# Peripheral.net
KiCad netlist of a schematic drawn in Altium Designer
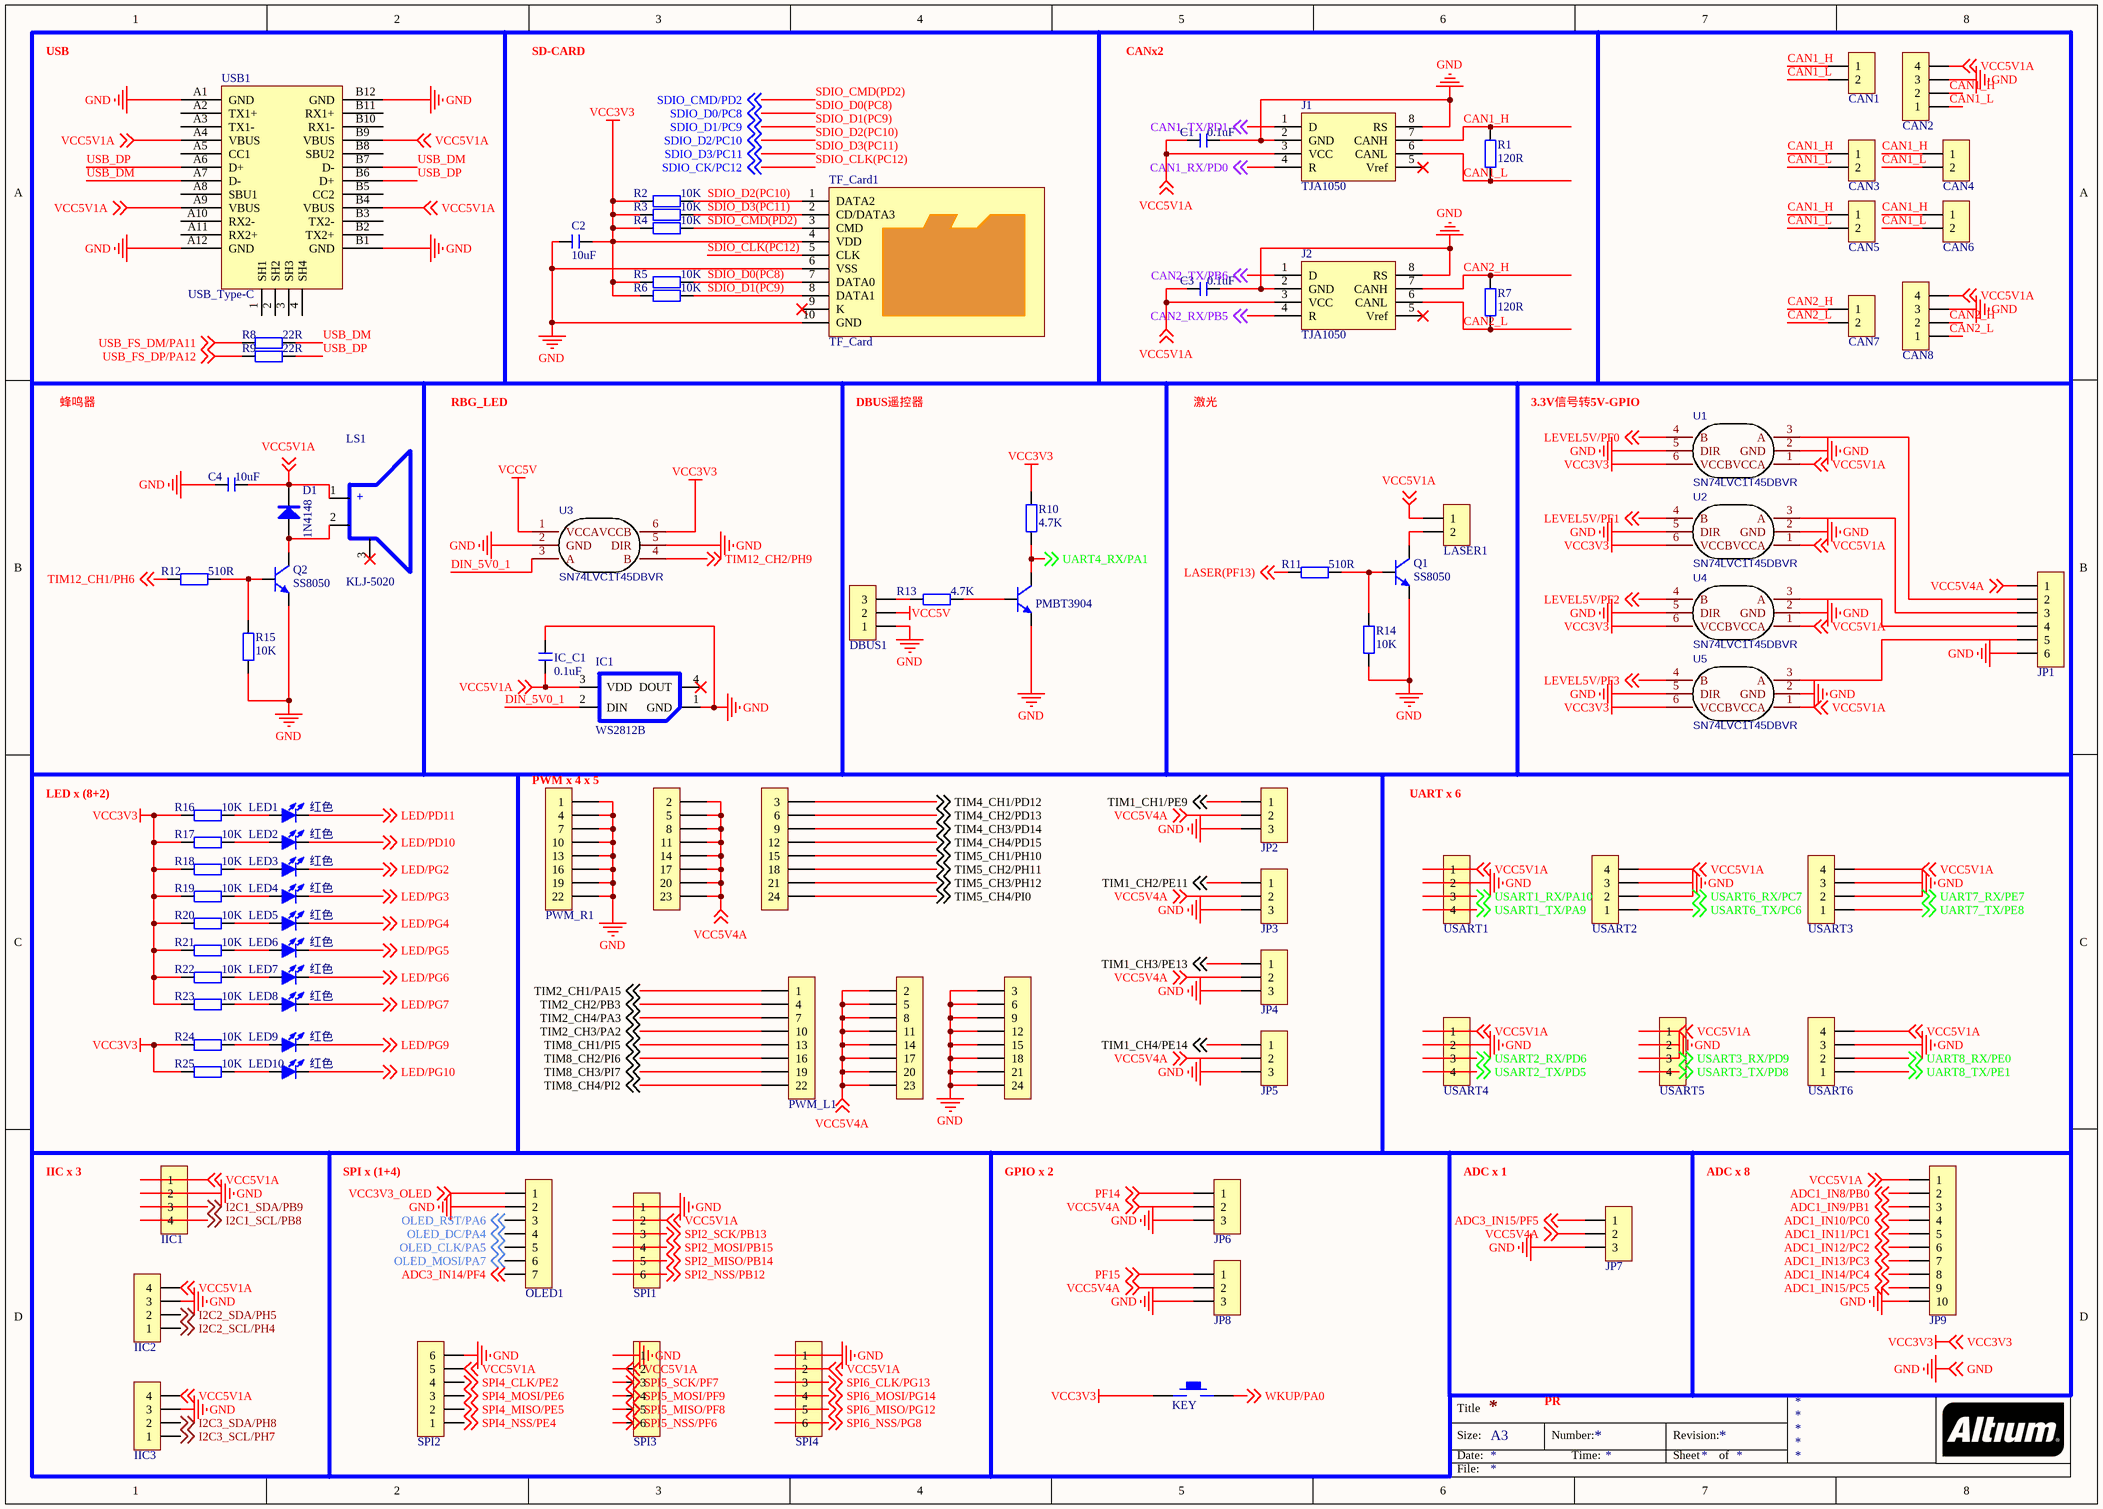
[diagram p0: Peripheral.SchDoc]

(export (version "E")
  (design (tool "Eeschema 10.0.6"))
  (components
    (comp (ref "C1")
      (value "0.1uF")
      (footprint "C 0402_L")
      (description "贴片电容")
      (libsource (lib "0.1 - 电阻-电容-电感") (part "C"))
    )
    (comp (ref "C2")
      (value "10uF")
      (footprint "C 0402_L")
      (description "贴片电容")
      (libsource (lib "0.1 - 电阻-电容-电感") (part "C"))
    )
    (comp (ref "C3")
      (value "0.1uF")
      (footprint "C 0402_L")
      (description "贴片电容")
      (libsource (lib "0.1 - 电阻-电容-电感") (part "C"))
    )
    (comp (ref "C4")
      (value "10uF")
      (footprint "C 0402_L")
      (description "贴片电容")
      (libsource (lib "0.1 - 电阻-电容-电感") (part "C"))
    )
    (comp (ref "CAN1")
      (value "HDR-1X2")
      (footprint "MX 1.25-LS-2P")
      (description "2P接插件")
      (libsource (lib "5.0 - 接插件-脚距1.25") (part "Header 2"))
    )
    (comp (ref "CAN2")
      (value "HDR-1X4")
      (footprint "MX 1.25-WS-4P")
      (description "4P接插件")
      (libsource (lib "") (part "Header 4_1"))
    )
    (comp (ref "CAN3")
      (value "HDR-1X2")
      (footprint "MX 1.25-LS-2P")
      (description "2P接插件")
      (libsource (lib "5.0 - 接插件-脚距1.25") (part "Header 2"))
    )
    (comp (ref "CAN4")
      (value "HDR-1X2")
      (footprint "MX 1.25-LS-2P")
      (description "2P接插件")
      (libsource (lib "5.0 - 接插件-脚距1.25") (part "Header 2"))
    )
    (comp (ref "CAN5")
      (value "HDR-1X2")
      (footprint "MX 1.25-LS-2P")
      (description "2P接插件")
      (libsource (lib "5.0 - 接插件-脚距1.25") (part "Header 2"))
    )
    (comp (ref "CAN6")
      (value "HDR-1X2")
      (footprint "MX 1.25-LS-2P")
      (description "2P接插件")
      (libsource (lib "5.0 - 接插件-脚距1.25") (part "Header 2"))
    )
    (comp (ref "CAN7")
      (value "HDR-1X2")
      (footprint "MX 1.25-LS-2P")
      (description "2P接插件")
      (libsource (lib "5.0 - 接插件-脚距1.25") (part "Header 2"))
    )
    (comp (ref "CAN8")
      (value "HDR-1X4")
      (footprint "MX 1.25-LS-4P")
      (description "4P接插件")
      (libsource (lib "") (part "Header 4_1"))
    )
    (comp (ref "D1")
      (value "1N4148")
      (footprint "SOD-323")
      (description "开关二极管")
      (libsource (lib "0.2 -  二极管-整流桥") (part "1N4148"))
    )
    (comp (ref "DBUS1")
      (value "HDR-1X3")
      (footprint "HDR2.54-WS-3P")
      (description "3P接插件")
      (libsource (lib "") (part "Header 3_1"))
    )
    (comp (ref "IC1")
      (value "WS2812B")
      (footprint "LED 3528-4Pin")
      (libsource (lib "mx_pcb_library") (part "WS2812B"))
    )
    (comp (ref "IC_C1")
      (value "0.1uF")
      (footprint "C 0402_L")
      (description "贴片电容")
      (libsource (lib "0.1 - 电阻-电容-电感") (part "C"))
    )
    (comp (ref "IIC1")
      (value "HDR-1X4")
      (footprint "MX 1.25-WS-4P")
      (description "4P接插件")
      (libsource (lib "5.0 - 接插件-脚距1.25") (part "Header 4"))
    )
    (comp (ref "IIC2")
      (value "HDR-1X4")
      (footprint "MX 1.25-LS-4P")
      (description "4P接插件")
      (libsource (lib "") (part "Header 4_1"))
    )
    (comp (ref "IIC3")
      (value "HDR-1X4")
      (footprint "MX 1.25-LS-4P")
      (description "4P接插件")
      (libsource (lib "") (part "Header 4_1"))
    )
    (comp (ref "J1")
      (value "TJA1050")
      (footprint "mx_pcb_library:SOIC-8_150mil")
      (description "CAN芯片")
      (libsource (lib "mx_pcb_library") (part "TJA1050"))
    )
    (comp (ref "J2")
      (value "TJA1050")
      (footprint "mx_pcb_library:SOIC-8_150mil")
      (description "CAN芯片")
      (libsource (lib "mx_pcb_library") (part "TJA1050"))
    )
    (comp (ref "JP1")
      (value "HDR-1X6")
      (footprint "MX 1.25-LS-6P")
      (description "6P接插件")
      (libsource (lib "5.0 - 接插件-脚距1.25") (part "Header 6"))
    )
    (comp (ref "JP2")
      (value "HDR-1X3")
      (footprint "HDR2.54-LI-3P")
      (description "3P接插件")
      (libsource (lib "5.3 - 接插件-脚距2.54 (100mil) ") (part "Header 3"))
    )
    (comp (ref "JP3")
      (value "HDR-1X3")
      (footprint "HDR2.54-LI-3P")
      (description "3P接插件")
      (libsource (lib "5.3 - 接插件-脚距2.54 (100mil) ") (part "Header 3"))
    )
    (comp (ref "JP4")
      (value "HDR-1X3")
      (footprint "HDR2.54-LI-3P")
      (description "3P接插件")
      (libsource (lib "5.3 - 接插件-脚距2.54 (100mil) ") (part "Header 3"))
    )
    (comp (ref "JP5")
      (value "HDR-1X3")
      (footprint "HDR2.54-LI-3P")
      (description "3P接插件")
      (libsource (lib "5.3 - 接插件-脚距2.54 (100mil) ") (part "Header 3"))
    )
    (comp (ref "JP6")
      (value "HDR-1X3")
      (footprint "HDR2.54-LI-3P")
      (description "3P接插件")
      (libsource (lib "5.3 - 接插件-脚距2.54 (100mil) ") (part "Header 3"))
    )
    (comp (ref "JP7")
      (value "HDR-1X3")
      (footprint "MX 1.25-WS-3P")
      (description "3P接插件")
      (libsource (lib "5.0 - 接插件-脚距1.25") (part "Header 3"))
    )
    (comp (ref "JP8")
      (value "HDR-1X3")
      (footprint "HDR2.54-LI-3P")
      (description "3P接插件")
      (libsource (lib "5.3 - 接插件-脚距2.54 (100mil) ") (part "Header 3"))
    )
    (comp (ref "JP9")
      (value "HDR-1X10")
      (footprint "MX 1.25-LS-10P")
      (description "10P接插件")
      (libsource (lib "5.0 - 接插件-脚距1.25") (part "Header 10"))
    )
    (comp (ref "LASER1")
      (value "HDR-1X2")
      (footprint "MX 1.25-LS-2P")
      (description "2P接插件")
      (libsource (lib "5.0 - 接插件-脚距1.25") (part "Header 2"))
    )
    (comp (ref "LED1")
      (value "红色")
      (footprint "LED 0805G")
      (description "贴片LED")
      (libsource (lib "0.3 - LED发光二极管") (part "LED-SMD"))
    )
    (comp (ref "LED2")
      (value "红色")
      (footprint "LED 0805G")
      (description "贴片LED")
      (libsource (lib "0.3 - LED发光二极管") (part "LED-SMD"))
    )
    (comp (ref "LED3")
      (value "红色")
      (footprint "LED 0805G")
      (description "贴片LED")
      (libsource (lib "0.3 - LED发光二极管") (part "LED-SMD"))
    )
    (comp (ref "LED4")
      (value "红色")
      (footprint "LED 0805G")
      (description "贴片LED")
      (libsource (lib "0.3 - LED发光二极管") (part "LED-SMD"))
    )
    (comp (ref "LED5")
      (value "红色")
      (footprint "LED 0805G")
      (description "贴片LED")
      (libsource (lib "0.3 - LED发光二极管") (part "LED-SMD"))
    )
    (comp (ref "LED6")
      (value "红色")
      (footprint "LED 0805G")
      (description "贴片LED")
      (libsource (lib "0.3 - LED发光二极管") (part "LED-SMD"))
    )
    (comp (ref "LED7")
      (value "红色")
      (footprint "LED 0805G")
      (description "贴片LED")
      (libsource (lib "0.3 - LED发光二极管") (part "LED-SMD"))
    )
    (comp (ref "LED8")
      (value "红色")
      (footprint "LED 0805G")
      (description "贴片LED")
      (libsource (lib "0.3 - LED发光二极管") (part "LED-SMD"))
    )
    (comp (ref "LED9")
      (value "红色")
      (footprint "LED 0805R")
      (description "贴片LED")
      (libsource (lib "0.3 - LED发光二极管") (part "LED-SMD"))
    )
    (comp (ref "LED10")
      (value "红色")
      (footprint "LED 0805R")
      (description "贴片LED")
      (libsource (lib "0.3 - LED发光二极管") (part "LED-SMD"))
    )
    (comp (ref "LS1")
      (value "KLJ-5020")
      (footprint "mx_pcb_library:BUZ-SMD_4P-L5.0-W5.0-P3.80-TL")
      (description "蜂鸣器")
      (libsource (lib "mx_pcb_library") (part "KLJ-5020"))
    )
    (comp (ref "OLED1")
      (value "HDR-1X7")
      (footprint "MX 1.25-WS-7P")
      (description "7P接插件")
      (libsource (lib "5.0 - 接插件-脚距1.25") (part "Header 7"))
    )
    (comp (ref "PWM_L1")
      (value "HDR3*8-left")
      (footprint "mx_pcb_library:PIN-3*8-2.54 - duplicate")
      (description "Connector")
      (libsource (lib "mx_pcb_library") (part "HDR3*8-left"))
    )
    (comp (ref "PWM_R1")
      (value "HDR3*8-right")
      (footprint "mx_pcb_library:PIN-3*8-2.54 - duplicate")
      (description "Connector")
      (libsource (lib "mx_pcb_library") (part "HDR3*8-right"))
    )
    (comp (ref "Q1")
      (value "SS8050")
      (footprint "SOT23-3L")
      (description "高频放大-NPN型")
      (libsource (lib "0.4 - 三极管") (part "8050-SMD"))
    )
    (comp (ref "Q2")
      (value "SS8050")
      (footprint "SOT23-3L")
      (description "高频放大-NPN型")
      (libsource (lib "0.4 - 三极管") (part "8050-SMD"))
    )
    (comp (ref "Q3")
      (value "PMBT3904")
      (footprint "mx_pcb_library:SOT-23-3")
      (description "NPN Bipolar Transistor")
      (libsource (lib "mx_pcb_library") (part "PMBT3904"))
    )
    (comp (ref "R1")
      (value "120R")
      (footprint "R 0402_L")
      (description "贴片电阻")
      (libsource (lib "0.1 - 电阻-电容-电感") (part "R"))
    )
    (comp (ref "R2")
      (value "10K")
      (footprint "R 0402_L")
      (description "贴片电阻")
      (libsource (lib "0.1 - 电阻-电容-电感") (part "R"))
    )
    (comp (ref "R3")
      (value "10K")
      (footprint "R 0402_L")
      (description "贴片电阻")
      (libsource (lib "0.1 - 电阻-电容-电感") (part "R"))
    )
    (comp (ref "R4")
      (value "10K")
      (footprint "R 0402_L")
      (description "贴片电阻")
      (libsource (lib "0.1 - 电阻-电容-电感") (part "R"))
    )
    (comp (ref "R5")
      (value "10K")
      (footprint "R 0402_L")
      (description "贴片电阻")
      (libsource (lib "0.1 - 电阻-电容-电感") (part "R"))
    )
    (comp (ref "R6")
      (value "10K")
      (footprint "R 0402_L")
      (description "贴片电阻")
      (libsource (lib "0.1 - 电阻-电容-电感") (part "R"))
    )
    (comp (ref "R7")
      (value "120R")
      (footprint "R 0402_L")
      (description "贴片电阻")
      (libsource (lib "0.1 - 电阻-电容-电感") (part "R"))
    )
    (comp (ref "R8")
      (value "22R")
      (footprint "R 0402_L")
      (description "贴片电阻")
      (libsource (lib "0.1 - 电阻-电容-电感") (part "R"))
    )
    (comp (ref "R9")
      (value "22R")
      (footprint "R 0402_L")
      (description "贴片电阻")
      (libsource (lib "0.1 - 电阻-电容-电感") (part "R"))
    )
    (comp (ref "R10")
      (value "4.7K")
      (footprint "R 0402_L")
      (description "贴片电阻")
      (libsource (lib "0.1 - 电阻-电容-电感") (part "R"))
    )
    (comp (ref "R11")
      (value "510R")
      (footprint "R 0402_L")
      (description "贴片电阻")
      (libsource (lib "0.1 - 电阻-电容-电感") (part "R"))
    )
    (comp (ref "R12")
      (value "510R")
      (footprint "R 0402_L")
      (description "贴片电阻")
      (libsource (lib "0.1 - 电阻-电容-电感") (part "R"))
    )
    (comp (ref "R13")
      (value "4.7K")
      (footprint "R 0402_L")
      (description "贴片电阻")
      (libsource (lib "0.1 - 电阻-电容-电感") (part "R"))
    )
    (comp (ref "R14")
      (value "10K")
      (footprint "R 0402_L")
      (description "贴片电阻")
      (libsource (lib "0.1 - 电阻-电容-电感") (part "R"))
    )
    (comp (ref "R15")
      (value "10K")
      (footprint "R 0402_L")
      (description "贴片电阻")
      (libsource (lib "0.1 - 电阻-电容-电感") (part "R"))
    )
    (comp (ref "R16")
      (value "10K")
      (footprint "R 0402_L")
      (description "贴片电阻")
      (libsource (lib "0.1 - 电阻-电容-电感") (part "R"))
    )
    (comp (ref "R17")
      (value "10K")
      (footprint "R 0402_L")
      (description "贴片电阻")
      (libsource (lib "0.1 - 电阻-电容-电感") (part "R"))
    )
    (comp (ref "R18")
      (value "10K")
      (footprint "R 0402_L")
      (description "贴片电阻")
      (libsource (lib "0.1 - 电阻-电容-电感") (part "R"))
    )
    (comp (ref "R19")
      (value "10K")
      (footprint "R 0402_L")
      (description "贴片电阻")
      (libsource (lib "0.1 - 电阻-电容-电感") (part "R"))
    )
    (comp (ref "R20")
      (value "10K")
      (footprint "R 0402_L")
      (description "贴片电阻")
      (libsource (lib "0.1 - 电阻-电容-电感") (part "R"))
    )
    (comp (ref "R21")
      (value "10K")
      (footprint "R 0402_L")
      (description "贴片电阻")
      (libsource (lib "0.1 - 电阻-电容-电感") (part "R"))
    )
    (comp (ref "R22")
      (value "10K")
      (footprint "R 0402_L")
      (description "贴片电阻")
      (libsource (lib "0.1 - 电阻-电容-电感") (part "R"))
    )
    (comp (ref "R23")
      (value "10K")
      (footprint "R 0402_L")
      (description "贴片电阻")
      (libsource (lib "0.1 - 电阻-电容-电感") (part "R"))
    )
    (comp (ref "R24")
      (value "10K")
      (footprint "R 0402_L")
      (description "贴片电阻")
      (libsource (lib "0.1 - 电阻-电容-电感") (part "R"))
    )
    (comp (ref "R25")
      (value "10K")
      (footprint "R 0402_L")
      (description "贴片电阻")
      (libsource (lib "0.1 - 电阻-电容-电感") (part "R"))
    )
    (comp (ref "RST1")
      (value "KEY")
      (footprint "mx_pcb_library:SMD-3.2*4.2")
      (libsource (lib "mx_pcb_library") (part "KEY_M"))
    )
    (comp (ref "SPI1")
      (value "HDR-1X6")
      (footprint "MX 1.25-WS-6P")
      (description "6P接插件")
      (libsource (lib "5.0 - 接插件-脚距1.25") (part "Header 6"))
    )
    (comp (ref "SPI2")
      (value "HDR-1X6")
      (footprint "MX 1.25-LS-6P")
      (description "6P接插件")
      (libsource (lib "") (part "Header 6_1"))
    )
    (comp (ref "SPI3")
      (value "HDR-1X6")
      (footprint "MX 1.25-WS-6P")
      (description "6P接插件")
      (libsource (lib "5.0 - 接插件-脚距1.25") (part "Header 6"))
    )
    (comp (ref "SPI4")
      (value "HDR-1X6")
      (footprint "MX 1.25-WS-6P")
      (description "6P接插件")
      (libsource (lib "5.0 - 接插件-脚距1.25") (part "Header 6"))
    )
    (comp (ref "TF_Card1")
      (value "TF_Card")
      (footprint "Micro SD")
      (description "TF卡座")
      (libsource (lib "0.8 - 网口-音频插座") (part "TF_Card"))
    )
    (comp (ref "U1")
      (value "SN74LVC1T45DBVR")
      (footprint "SOT-23-6_L2.9-W1.6-P0.95-LS2.8-BL")
      (fields (field (name "BOM_SUPPLIER PART") "C7843"))
      (libsource (lib "mx_pcb_library") (part "SN74LVC1T45DBVR"))
    )
    (comp (ref "U2")
      (value "SN74LVC1T45DBVR")
      (footprint "SOT-23-6_L2.9-W1.6-P0.95-LS2.8-BL")
      (fields (field (name "BOM_SUPPLIER PART") "C7843"))
      (libsource (lib "mx_pcb_library") (part "SN74LVC1T45DBVR"))
    )
    (comp (ref "U3")
      (value "SN74LVC1T45DBVR")
      (footprint "SOT-23-6_L2.9-W1.6-P0.95-LS2.8-BL")
      (fields (field (name "BOM_SUPPLIER PART") "C7843"))
      (libsource (lib "mx_pcb_library") (part "SN74LVC1T45DBVR"))
    )
    (comp (ref "U4")
      (value "SN74LVC1T45DBVR")
      (footprint "SOT-23-6_L2.9-W1.6-P0.95-LS2.8-BL")
      (fields (field (name "BOM_SUPPLIER PART") "C7843"))
      (libsource (lib "mx_pcb_library") (part "SN74LVC1T45DBVR"))
    )
    (comp (ref "U5")
      (value "SN74LVC1T45DBVR")
      (footprint "SOT-23-6_L2.9-W1.6-P0.95-LS2.8-BL")
      (fields (field (name "BOM_SUPPLIER PART") "C7843"))
      (libsource (lib "mx_pcb_library") (part "SN74LVC1T45DBVR"))
    )
    (comp (ref "USART1")
      (value "HDR-1X4")
      (footprint "MX 1.25-LS-4P")
      (description "4P接插件")
      (libsource (lib "5.0 - 接插件-脚距1.25") (part "Header 4"))
    )
    (comp (ref "USART2")
      (value "HDR-1X4")
      (footprint "MX 1.25-WS-4P")
      (description "4P接插件")
      (libsource (lib "") (part "Header 4_1"))
    )
    (comp (ref "USART3")
      (value "HDR-1X4")
      (footprint "MX 1.25-WS-4P")
      (description "4P接插件")
      (libsource (lib "") (part "Header 4_1"))
    )
    (comp (ref "USART4")
      (value "HDR-1X4")
      (footprint "MX 1.25-LS-4P")
      (description "4P接插件")
      (libsource (lib "5.0 - 接插件-脚距1.25") (part "Header 4"))
    )
    (comp (ref "USART5")
      (value "HDR-1X4")
      (footprint "MX 1.25-LS-4P")
      (description "4P接插件")
      (libsource (lib "5.0 - 接插件-脚距1.25") (part "Header 4"))
    )
    (comp (ref "USART6")
      (value "HDR-1X4")
      (footprint "MX 1.25-WS-4P")
      (description "4P接插件")
      (libsource (lib "") (part "Header 4_1"))
    )
    (comp (ref "USB1")
      (value "USB_Type-C")
      (footprint "mx_pcb_library:Type-C-TOP")
      (libsource (lib "mx_pcb_library") (part "USB_Type-C"))
    )
  )
  (nets
    (net (code "1") (name "/CAN1_H") (class "Default")
      (node (ref "CAN1") (pin "1") (pinfunction "1_1") (pintype "passive"))
      (node (ref "CAN2") (pin "2") (pinfunction "2_2") (pintype "passive"))
      (node (ref "CAN3") (pin "1") (pinfunction "1_1") (pintype "passive"))
      (node (ref "CAN4") (pin "1") (pinfunction "1_1") (pintype "passive"))
      (node (ref "CAN5") (pin "1") (pinfunction "1_1") (pintype "passive"))
      (node (ref "CAN6") (pin "1") (pinfunction "1_1") (pintype "passive"))
      (node (ref "J1") (pin "7") (pinfunction "CANH_7") (pintype "passive"))
      (node (ref "R1") (pin "2") (pinfunction "2_2") (pintype "passive"))
    )
    (net (code "2") (name "/CAN1_L") (class "Default")
      (node (ref "CAN1") (pin "2") (pinfunction "2_2") (pintype "passive"))
      (node (ref "CAN2") (pin "1") (pinfunction "1_1") (pintype "passive"))
      (node (ref "CAN3") (pin "2") (pinfunction "2_2") (pintype "passive"))
      (node (ref "CAN4") (pin "2") (pinfunction "2_2") (pintype "passive"))
      (node (ref "CAN5") (pin "2") (pinfunction "2_2") (pintype "passive"))
      (node (ref "CAN6") (pin "2") (pinfunction "2_2") (pintype "passive"))
      (node (ref "J1") (pin "6") (pinfunction "CANL_6") (pintype "passive"))
      (node (ref "R1") (pin "1") (pinfunction "1_1") (pintype "passive"))
    )
    (net (code "3") (name "/CAN2_H") (class "Default")
      (node (ref "CAN7") (pin "1") (pinfunction "1_1") (pintype "passive"))
      (node (ref "CAN8") (pin "2") (pinfunction "2_2") (pintype "passive"))
      (node (ref "J2") (pin "7") (pinfunction "CANH_7") (pintype "passive"))
      (node (ref "R7") (pin "2") (pinfunction "2_2") (pintype "passive"))
    )
    (net (code "4") (name "/CAN2_L") (class "Default")
      (node (ref "CAN7") (pin "2") (pinfunction "2_2") (pintype "passive"))
      (node (ref "CAN8") (pin "1") (pinfunction "1_1") (pintype "passive"))
      (node (ref "J2") (pin "6") (pinfunction "CANL_6") (pintype "passive"))
      (node (ref "R7") (pin "1") (pinfunction "1_1") (pintype "passive"))
    )
    (net (code "5") (name "/DIN_5V0_1") (class "Default")
      (node (ref "IC1") (pin "2") (pinfunction "DIN_2") (pintype "passive"))
      (node (ref "U3") (pin "3") (pinfunction "A_3") (pintype "passive"))
    )
    (net (code "6") (name "/USB_DM") (class "Default")
      (node (ref "R8") (pin "2") (pinfunction "2_2") (pintype "passive"))
      (node (ref "USB1") (pin "A7") (pinfunction "D-_A7") (pintype "passive"))
      (node (ref "USB1") (pin "B7") (pinfunction "D-_B7") (pintype "passive"))
    )
    (net (code "7") (name "/USB_DP") (class "Default")
      (node (ref "R9") (pin "2") (pinfunction "2_2") (pintype "passive"))
      (node (ref "USB1") (pin "A6") (pinfunction "D+_A6") (pintype "passive"))
      (node (ref "USB1") (pin "B6") (pinfunction "D+_B6") (pintype "passive"))
    )
    (net (code "8") (name "ADC1_IN8{slash}PB0") (class "Default")
      (node (ref "JP9") (pin "2") (pinfunction "2_2") (pintype "passive"))
    )
    (net (code "9") (name "ADC1_IN9{slash}PB1") (class "Default")
      (node (ref "JP9") (pin "3") (pinfunction "3_3") (pintype "passive"))
    )
    (net (code "10") (name "ADC1_IN10{slash}PC0") (class "Default")
      (node (ref "JP9") (pin "4") (pinfunction "4_4") (pintype "passive"))
    )
    (net (code "11") (name "ADC1_IN11{slash}PC1") (class "Default")
      (node (ref "JP9") (pin "5") (pinfunction "5_5") (pintype "passive"))
    )
    (net (code "12") (name "ADC1_IN12{slash}PC2") (class "Default")
      (node (ref "JP9") (pin "6") (pinfunction "6_6") (pintype "passive"))
    )
    (net (code "13") (name "ADC1_IN13{slash}PC3") (class "Default")
      (node (ref "JP9") (pin "7") (pinfunction "7_7") (pintype "passive"))
    )
    (net (code "14") (name "ADC1_IN14{slash}PC4") (class "Default")
      (node (ref "JP9") (pin "8") (pinfunction "8_8") (pintype "passive"))
    )
    (net (code "15") (name "ADC1_IN15{slash}PC5") (class "Default")
      (node (ref "JP9") (pin "9") (pinfunction "9_9") (pintype "passive"))
    )
    (net (code "16") (name "ADC3_IN14{slash}PF4") (class "Default")
      (node (ref "OLED1") (pin "7") (pinfunction "7_7") (pintype "passive"))
    )
    (net (code "17") (name "ADC3_IN15{slash}PF5") (class "Default")
      (node (ref "JP7") (pin "1") (pinfunction "1_1") (pintype "passive"))
    )
    (net (code "18") (name "CAN1_RX{slash}PD0") (class "Default")
      (node (ref "J1") (pin "4") (pinfunction "R_4") (pintype "passive"))
    )
    (net (code "19") (name "CAN1_TX{slash}PD1") (class "Default")
      (node (ref "J1") (pin "1") (pinfunction "D_1") (pintype "passive"))
    )
    (net (code "20") (name "CAN2_RX{slash}PB5") (class "Default")
      (node (ref "J2") (pin "4") (pinfunction "R_4") (pintype "passive"))
    )
    (net (code "21") (name "CAN2_TX{slash}PB6") (class "Default")
      (node (ref "J2") (pin "1") (pinfunction "D_1") (pintype "passive"))
    )
    (net (code "22") (name "GND") (class "Default")
      (node (ref "C1") (pin "1") (pinfunction "1_1") (pintype "passive"))
      (node (ref "C2") (pin "1") (pinfunction "1_1") (pintype "passive"))
      (node (ref "C3") (pin "1") (pinfunction "1_1") (pintype "passive"))
      (node (ref "C4") (pin "2") (pinfunction "2_2") (pintype "passive"))
      (node (ref "CAN2") (pin "3") (pinfunction "3_3") (pintype "passive"))
      (node (ref "CAN8") (pin "3") (pinfunction "3_3") (pintype "passive"))
      (node (ref "DBUS1") (pin "1") (pinfunction "1_1") (pintype "passive"))
      (node (ref "IC1") (pin "1") (pinfunction "GND_1") (pintype "passive"))
      (node (ref "IC_C1") (pin "1") (pinfunction "1_1") (pintype "passive"))
      (node (ref "IIC1") (pin "2") (pinfunction "2_2") (pintype "passive"))
      (node (ref "IIC2") (pin "3") (pinfunction "3_3") (pintype "passive"))
      (node (ref "IIC3") (pin "3") (pinfunction "3_3") (pintype "passive"))
      (node (ref "J1") (pin "2") (pinfunction "GND_2") (pintype "passive"))
      (node (ref "J1") (pin "8") (pinfunction "RS_8") (pintype "passive"))
      (node (ref "J2") (pin "2") (pinfunction "GND_2") (pintype "passive"))
      (node (ref "J2") (pin "8") (pinfunction "RS_8") (pintype "passive"))
      (node (ref "JP1") (pin "6") (pinfunction "6_6") (pintype "passive"))
      (node (ref "JP2") (pin "3") (pinfunction "3_3") (pintype "passive"))
      (node (ref "JP3") (pin "3") (pinfunction "3_3") (pintype "passive"))
      (node (ref "JP4") (pin "3") (pinfunction "3_3") (pintype "passive"))
      (node (ref "JP5") (pin "3") (pinfunction "3_3") (pintype "passive"))
      (node (ref "JP6") (pin "3") (pinfunction "3_3") (pintype "passive"))
      (node (ref "JP7") (pin "3") (pinfunction "3_3") (pintype "passive"))
      (node (ref "JP8") (pin "3") (pinfunction "3_3") (pintype "passive"))
      (node (ref "JP9") (pin "10") (pinfunction "10_10") (pintype "passive"))
      (node (ref "OLED1") (pin "2") (pinfunction "2_2") (pintype "passive"))
      (node (ref "PWM_L1") (pin "12") (pinfunction "12_12") (pintype "passive"))
      (node (ref "PWM_L1") (pin "15") (pinfunction "15_15") (pintype "passive"))
      (node (ref "PWM_L1") (pin "18") (pinfunction "18_18") (pintype "passive"))
      (node (ref "PWM_L1") (pin "21") (pinfunction "21_21") (pintype "passive"))
      (node (ref "PWM_L1") (pin "24") (pinfunction "24_24") (pintype "passive"))
      (node (ref "PWM_L1") (pin "3") (pinfunction "3_3") (pintype "passive"))
      (node (ref "PWM_L1") (pin "6") (pinfunction "6_6") (pintype "passive"))
      (node (ref "PWM_L1") (pin "9") (pinfunction "9_9") (pintype "passive"))
      (node (ref "PWM_R1") (pin "1") (pinfunction "1_1") (pintype "passive"))
      (node (ref "PWM_R1") (pin "10") (pinfunction "10_10") (pintype "passive"))
      (node (ref "PWM_R1") (pin "13") (pinfunction "13_13") (pintype "passive"))
      (node (ref "PWM_R1") (pin "16") (pinfunction "16_16") (pintype "passive"))
      (node (ref "PWM_R1") (pin "19") (pinfunction "19_19") (pintype "passive"))
      (node (ref "PWM_R1") (pin "22") (pinfunction "22_22") (pintype "passive"))
      (node (ref "PWM_R1") (pin "4") (pinfunction "4_4") (pintype "passive"))
      (node (ref "PWM_R1") (pin "7") (pinfunction "7_7") (pintype "passive"))
      (node (ref "Q1") (pin "2") (pinfunction "E_2") (pintype "passive"))
      (node (ref "Q2") (pin "2") (pinfunction "E_2") (pintype "passive"))
      (node (ref "Q3") (pin "2") (pinfunction "E_2") (pintype "passive"))
      (node (ref "R14") (pin "1") (pinfunction "1_1") (pintype "passive"))
      (node (ref "R15") (pin "1") (pinfunction "1_1") (pintype "passive"))
      (node (ref "SPI1") (pin "1") (pinfunction "1_1") (pintype "passive"))
      (node (ref "SPI2") (pin "6") (pinfunction "6_6") (pintype "passive"))
      (node (ref "SPI3") (pin "1") (pinfunction "1_1") (pintype "passive"))
      (node (ref "SPI4") (pin "1") (pinfunction "1_1") (pintype "passive"))
      (node (ref "TF_Card1") (pin "10") (pinfunction "GND_10") (pintype "passive"))
      (node (ref "TF_Card1") (pin "6") (pinfunction "VSS_6") (pintype "passive"))
      (node (ref "U1") (pin "2") (pinfunction "GND_2") (pintype "passive"))
      (node (ref "U1") (pin "5") (pinfunction "DIR_5") (pintype "passive"))
      (node (ref "U2") (pin "2") (pinfunction "GND_2") (pintype "passive"))
      (node (ref "U2") (pin "5") (pinfunction "DIR_5") (pintype "passive"))
      (node (ref "U3") (pin "2") (pinfunction "GND_2") (pintype "passive"))
      (node (ref "U3") (pin "5") (pinfunction "DIR_5") (pintype "passive"))
      (node (ref "U4") (pin "2") (pinfunction "GND_2") (pintype "passive"))
      (node (ref "U4") (pin "5") (pinfunction "DIR_5") (pintype "passive"))
      (node (ref "U5") (pin "2") (pinfunction "GND_2") (pintype "passive"))
      (node (ref "U5") (pin "5") (pinfunction "DIR_5") (pintype "passive"))
      (node (ref "USART1") (pin "2") (pinfunction "2_2") (pintype "passive"))
      (node (ref "USART2") (pin "3") (pinfunction "3_3") (pintype "passive"))
      (node (ref "USART3") (pin "3") (pinfunction "3_3") (pintype "passive"))
      (node (ref "USART4") (pin "2") (pinfunction "2_2") (pintype "passive"))
      (node (ref "USART5") (pin "2") (pinfunction "2_2") (pintype "passive"))
      (node (ref "USART6") (pin "3") (pinfunction "3_3") (pintype "passive"))
      (node (ref "USB1") (pin "A1") (pinfunction "GND_A1") (pintype "passive"))
      (node (ref "USB1") (pin "A12") (pinfunction "GND_A12") (pintype "passive"))
      (node (ref "USB1") (pin "B1") (pinfunction "GND_B1") (pintype "passive"))
      (node (ref "USB1") (pin "B12") (pinfunction "GND_B12") (pintype "passive"))
    )
    (net (code "23") (name "I2C1_SCL{slash}PB8") (class "Default")
      (node (ref "IIC1") (pin "4") (pinfunction "4_4") (pintype "passive"))
    )
    (net (code "24") (name "I2C1_SDA{slash}PB9") (class "Default")
      (node (ref "IIC1") (pin "3") (pinfunction "3_3") (pintype "passive"))
    )
    (net (code "25") (name "I2C2_SCL{slash}PH4") (class "Default")
      (node (ref "IIC2") (pin "1") (pinfunction "1_1") (pintype "passive"))
    )
    (net (code "26") (name "I2C2_SDA{slash}PH5") (class "Default")
      (node (ref "IIC2") (pin "2") (pinfunction "2_2") (pintype "passive"))
    )
    (net (code "27") (name "I2C3_SCL{slash}PH7") (class "Default")
      (node (ref "IIC3") (pin "1") (pinfunction "1_1") (pintype "passive"))
    )
    (net (code "28") (name "I2C3_SDA{slash}PH8") (class "Default")
      (node (ref "IIC3") (pin "2") (pinfunction "2_2") (pintype "passive"))
    )
    (net (code "29") (name "LASER(PF13)") (class "Default")
      (node (ref "R11") (pin "1") (pinfunction "1_1") (pintype "passive"))
    )
    (net (code "30") (name "LED{slash}PD10") (class "Default")
      (node (ref "LED2") (pin "2") (pinfunction "K_2") (pintype "passive"))
    )
    (net (code "31") (name "LED{slash}PD11") (class "Default")
      (node (ref "LED1") (pin "2") (pinfunction "K_2") (pintype "passive"))
    )
    (net (code "32") (name "LED{slash}PG2") (class "Default")
      (node (ref "LED3") (pin "2") (pinfunction "K_2") (pintype "passive"))
    )
    (net (code "33") (name "LED{slash}PG3") (class "Default")
      (node (ref "LED4") (pin "2") (pinfunction "K_2") (pintype "passive"))
    )
    (net (code "34") (name "LED{slash}PG4") (class "Default")
      (node (ref "LED5") (pin "2") (pinfunction "K_2") (pintype "passive"))
    )
    (net (code "35") (name "LED{slash}PG5") (class "Default")
      (node (ref "LED6") (pin "2") (pinfunction "K_2") (pintype "passive"))
    )
    (net (code "36") (name "LED{slash}PG6") (class "Default")
      (node (ref "LED7") (pin "2") (pinfunction "K_2") (pintype "passive"))
    )
    (net (code "37") (name "LED{slash}PG7") (class "Default")
      (node (ref "LED8") (pin "2") (pinfunction "K_2") (pintype "passive"))
    )
    (net (code "38") (name "LED{slash}PG9") (class "Default")
      (node (ref "LED9") (pin "2") (pinfunction "K_2") (pintype "passive"))
    )
    (net (code "39") (name "LED{slash}PG10") (class "Default")
      (node (ref "LED10") (pin "2") (pinfunction "K_2") (pintype "passive"))
    )
    (net (code "40") (name "LEVEL5V{slash}PF0") (class "Default")
      (node (ref "U1") (pin "4") (pinfunction "B_4") (pintype "passive"))
    )
    (net (code "41") (name "LEVEL5V{slash}PF1") (class "Default")
      (node (ref "U2") (pin "4") (pinfunction "B_4") (pintype "passive"))
    )
    (net (code "42") (name "LEVEL5V{slash}PF2") (class "Default")
      (node (ref "U4") (pin "4") (pinfunction "B_4") (pintype "passive"))
    )
    (net (code "43") (name "LEVEL5V{slash}PF3") (class "Default")
      (node (ref "U5") (pin "4") (pinfunction "B_4") (pintype "passive"))
    )
    (net (code "44") (name "Net-(D1-A)") (class "Default")
      (node (ref "D1") (pin "1") (pinfunction "A_1") (pintype "passive"))
      (node (ref "LS1") (pin "2") (pinfunction "2_2") (pintype "passive"))
      (node (ref "Q2") (pin "3") (pinfunction "C_3") (pintype "passive"))
    )
    (net (code "45") (name "Net-(DBUS1-Pad3)") (class "Default")
      (node (ref "DBUS1") (pin "3") (pinfunction "3_3") (pintype "passive"))
      (node (ref "R13") (pin "2") (pinfunction "2_2") (pintype "passive"))
    )
    (net (code "46") (name "Net-(LED1-A)") (class "Default")
      (node (ref "LED1") (pin "1") (pinfunction "A_1") (pintype "passive"))
      (node (ref "R16") (pin "2") (pinfunction "2_2") (pintype "passive"))
    )
    (net (code "47") (name "Net-(LED2-A)") (class "Default")
      (node (ref "LED2") (pin "1") (pinfunction "A_1") (pintype "passive"))
      (node (ref "R17") (pin "2") (pinfunction "2_2") (pintype "passive"))
    )
    (net (code "48") (name "Net-(LED3-A)") (class "Default")
      (node (ref "LED3") (pin "1") (pinfunction "A_1") (pintype "passive"))
      (node (ref "R18") (pin "2") (pinfunction "2_2") (pintype "passive"))
    )
    (net (code "49") (name "Net-(LED4-A)") (class "Default")
      (node (ref "LED4") (pin "1") (pinfunction "A_1") (pintype "passive"))
      (node (ref "R19") (pin "2") (pinfunction "2_2") (pintype "passive"))
    )
    (net (code "50") (name "Net-(LED5-A)") (class "Default")
      (node (ref "LED5") (pin "1") (pinfunction "A_1") (pintype "passive"))
      (node (ref "R20") (pin "2") (pinfunction "2_2") (pintype "passive"))
    )
    (net (code "51") (name "Net-(LED6-A)") (class "Default")
      (node (ref "LED6") (pin "1") (pinfunction "A_1") (pintype "passive"))
      (node (ref "R21") (pin "2") (pinfunction "2_2") (pintype "passive"))
    )
    (net (code "52") (name "Net-(LED7-A)") (class "Default")
      (node (ref "LED7") (pin "1") (pinfunction "A_1") (pintype "passive"))
      (node (ref "R22") (pin "2") (pinfunction "2_2") (pintype "passive"))
    )
    (net (code "53") (name "Net-(LED8-A)") (class "Default")
      (node (ref "LED8") (pin "1") (pinfunction "A_1") (pintype "passive"))
      (node (ref "R23") (pin "2") (pinfunction "2_2") (pintype "passive"))
    )
    (net (code "54") (name "Net-(LED9-A)") (class "Default")
      (node (ref "LED9") (pin "1") (pinfunction "A_1") (pintype "passive"))
      (node (ref "R24") (pin "2") (pinfunction "2_2") (pintype "passive"))
    )
    (net (code "55") (name "Net-(LED10-A)") (class "Default")
      (node (ref "LED10") (pin "1") (pinfunction "A_1") (pintype "passive"))
      (node (ref "R25") (pin "2") (pinfunction "2_2") (pintype "passive"))
    )
    (net (code "56") (name "Net-(Q1-B)") (class "Default")
      (node (ref "Q1") (pin "1") (pinfunction "B_1") (pintype "passive"))
      (node (ref "R11") (pin "2") (pinfunction "2_2") (pintype "passive"))
      (node (ref "R14") (pin "2") (pinfunction "2_2") (pintype "passive"))
    )
    (net (code "57") (name "Net-(Q1-C)") (class "Default")
      (node (ref "LASER1") (pin "2") (pinfunction "2_2") (pintype "passive"))
      (node (ref "Q1") (pin "3") (pinfunction "C_3") (pintype "passive"))
    )
    (net (code "58") (name "Net-(Q2-B)") (class "Default")
      (node (ref "Q2") (pin "1") (pinfunction "B_1") (pintype "passive"))
      (node (ref "R12") (pin "2") (pinfunction "2_2") (pintype "passive"))
      (node (ref "R15") (pin "2") (pinfunction "2_2") (pintype "passive"))
    )
    (net (code "59") (name "Net-(Q3-B)") (class "Default")
      (node (ref "Q3") (pin "1") (pinfunction "B_1") (pintype "passive"))
      (node (ref "R13") (pin "1") (pinfunction "1_1") (pintype "passive"))
    )
    (net (code "60") (name "Net-(U1-A)") (class "Default")
      (node (ref "JP1") (pin "2") (pinfunction "2_2") (pintype "passive"))
      (node (ref "U1") (pin "3") (pinfunction "A_3") (pintype "passive"))
    )
    (net (code "61") (name "Net-(U2-A)") (class "Default")
      (node (ref "JP1") (pin "3") (pinfunction "3_3") (pintype "passive"))
      (node (ref "U2") (pin "3") (pinfunction "A_3") (pintype "passive"))
    )
    (net (code "62") (name "Net-(U4-A)") (class "Default")
      (node (ref "JP1") (pin "4") (pinfunction "4_4") (pintype "passive"))
      (node (ref "U4") (pin "3") (pinfunction "A_3") (pintype "passive"))
    )
    (net (code "63") (name "Net-(U5-A)") (class "Default")
      (node (ref "JP1") (pin "5") (pinfunction "5_5") (pintype "passive"))
      (node (ref "U5") (pin "3") (pinfunction "A_3") (pintype "passive"))
    )
    (net (code "64") (name "OLED_CLK{slash}PA5") (class "Default")
      (node (ref "OLED1") (pin "5") (pinfunction "5_5") (pintype "passive"))
    )
    (net (code "65") (name "OLED_DC{slash}PA4") (class "Default")
      (node (ref "OLED1") (pin "4") (pinfunction "4_4") (pintype "passive"))
    )
    (net (code "66") (name "OLED_MOSI{slash}PA7") (class "Default")
      (node (ref "OLED1") (pin "6") (pinfunction "6_6") (pintype "passive"))
    )
    (net (code "67") (name "OLED_RST{slash}PA6") (class "Default")
      (node (ref "OLED1") (pin "3") (pinfunction "3_3") (pintype "passive"))
    )
    (net (code "68") (name "PF14") (class "Default")
      (node (ref "JP6") (pin "1") (pinfunction "1_1") (pintype "passive"))
    )
    (net (code "69") (name "PF15") (class "Default")
      (node (ref "JP8") (pin "1") (pinfunction "1_1") (pintype "passive"))
    )
    (net (code "70") (name "SDIO_CK{slash}PC12") (class "Default")
      (node (ref "TF_Card1") (pin "5") (pinfunction "CLK_5") (pintype "passive"))
    )
    (net (code "71") (name "SDIO_CMD{slash}PD2") (class "Default")
      (node (ref "R4") (pin "2") (pinfunction "2_2") (pintype "passive"))
      (node (ref "TF_Card1") (pin "3") (pinfunction "CMD_3") (pintype "passive"))
    )
    (net (code "72") (name "SDIO_D0{slash}PC8") (class "Default")
      (node (ref "R5") (pin "2") (pinfunction "2_2") (pintype "passive"))
      (node (ref "TF_Card1") (pin "7") (pinfunction "DATA0_7") (pintype "passive"))
    )
    (net (code "73") (name "SDIO_D1{slash}PC9") (class "Default")
      (node (ref "R6") (pin "2") (pinfunction "2_2") (pintype "passive"))
      (node (ref "TF_Card1") (pin "8") (pinfunction "DATA1_8") (pintype "passive"))
    )
    (net (code "74") (name "SDIO_D2{slash}PC10") (class "Default")
      (node (ref "R2") (pin "2") (pinfunction "2_2") (pintype "passive"))
      (node (ref "TF_Card1") (pin "1") (pinfunction "DATA2_1") (pintype "passive"))
    )
    (net (code "75") (name "SDIO_D3{slash}PC11") (class "Default")
      (node (ref "R3") (pin "2") (pinfunction "2_2") (pintype "passive"))
      (node (ref "TF_Card1") (pin "2") (pinfunction "CD/DATA3_2") (pintype "passive"))
    )
    (net (code "76") (name "SPI2_MISO{slash}PB14") (class "Default")
      (node (ref "SPI1") (pin "5") (pinfunction "5_5") (pintype "passive"))
    )
    (net (code "77") (name "SPI2_MOSI{slash}PB15") (class "Default")
      (node (ref "SPI1") (pin "4") (pinfunction "4_4") (pintype "passive"))
    )
    (net (code "78") (name "SPI2_NSS{slash}PB12") (class "Default")
      (node (ref "SPI1") (pin "6") (pinfunction "6_6") (pintype "passive"))
    )
    (net (code "79") (name "SPI2_SCK{slash}PB13") (class "Default")
      (node (ref "SPI1") (pin "3") (pinfunction "3_3") (pintype "passive"))
    )
    (net (code "80") (name "SPI4_CLK{slash}PE2") (class "Default")
      (node (ref "SPI2") (pin "4") (pinfunction "4_4") (pintype "passive"))
    )
    (net (code "81") (name "SPI4_MISO{slash}PE5") (class "Default")
      (node (ref "SPI2") (pin "2") (pinfunction "2_2") (pintype "passive"))
    )
    (net (code "82") (name "SPI4_MOSI{slash}PE6") (class "Default")
      (node (ref "SPI2") (pin "3") (pinfunction "3_3") (pintype "passive"))
    )
    (net (code "83") (name "SPI4_NSS{slash}PE4") (class "Default")
      (node (ref "SPI2") (pin "1") (pinfunction "1_1") (pintype "passive"))
    )
    (net (code "84") (name "SPI5_MISO{slash}PF8") (class "Default")
      (node (ref "SPI3") (pin "5") (pinfunction "5_5") (pintype "passive"))
    )
    (net (code "85") (name "SPI5_MOSI{slash}PF9") (class "Default")
      (node (ref "SPI3") (pin "4") (pinfunction "4_4") (pintype "passive"))
    )
    (net (code "86") (name "SPI5_NSS{slash}PF6") (class "Default")
      (node (ref "SPI3") (pin "6") (pinfunction "6_6") (pintype "passive"))
    )
    (net (code "87") (name "SPI5_SCK{slash}PF7") (class "Default")
      (node (ref "SPI3") (pin "3") (pinfunction "3_3") (pintype "passive"))
    )
    (net (code "88") (name "SPI6_CLK{slash}PG13") (class "Default")
      (node (ref "SPI4") (pin "3") (pinfunction "3_3") (pintype "passive"))
    )
    (net (code "89") (name "SPI6_MISO{slash}PG12") (class "Default")
      (node (ref "SPI4") (pin "5") (pinfunction "5_5") (pintype "passive"))
    )
    (net (code "90") (name "SPI6_MOSI{slash}PG14") (class "Default")
      (node (ref "SPI4") (pin "4") (pinfunction "4_4") (pintype "passive"))
    )
    (net (code "91") (name "SPI6_NSS{slash}PG8") (class "Default")
      (node (ref "SPI4") (pin "6") (pinfunction "6_6") (pintype "passive"))
    )
    (net (code "92") (name "TIM1_CH1{slash}PE9") (class "Default")
      (node (ref "JP2") (pin "1") (pinfunction "1_1") (pintype "passive"))
    )
    (net (code "93") (name "TIM1_CH2{slash}PE11") (class "Default")
      (node (ref "JP3") (pin "1") (pinfunction "1_1") (pintype "passive"))
    )
    (net (code "94") (name "TIM1_CH3{slash}PE13") (class "Default")
      (node (ref "JP4") (pin "1") (pinfunction "1_1") (pintype "passive"))
    )
    (net (code "95") (name "TIM1_CH4{slash}PE14") (class "Default")
      (node (ref "JP5") (pin "1") (pinfunction "1_1") (pintype "passive"))
    )
    (net (code "96") (name "TIM2_CH1{slash}PA15") (class "Default")
      (node (ref "PWM_L1") (pin "1") (pinfunction "1_1") (pintype "passive"))
    )
    (net (code "97") (name "TIM2_CH2{slash}PB3") (class "Default")
      (node (ref "PWM_L1") (pin "4") (pinfunction "4_4") (pintype "passive"))
    )
    (net (code "98") (name "TIM2_CH3{slash}PA2") (class "Default")
      (node (ref "PWM_L1") (pin "10") (pinfunction "10_10") (pintype "passive"))
    )
    (net (code "99") (name "TIM2_CH4{slash}PA3") (class "Default")
      (node (ref "PWM_L1") (pin "7") (pinfunction "7_7") (pintype "passive"))
    )
    (net (code "100") (name "TIM4_CH1{slash}PD12") (class "Default")
      (node (ref "PWM_R1") (pin "3") (pinfunction "3_3") (pintype "passive"))
    )
    (net (code "101") (name "TIM4_CH2{slash}PD13") (class "Default")
      (node (ref "PWM_R1") (pin "6") (pinfunction "6_6") (pintype "passive"))
    )
    (net (code "102") (name "TIM4_CH3{slash}PD14") (class "Default")
      (node (ref "PWM_R1") (pin "9") (pinfunction "9_9") (pintype "passive"))
    )
    (net (code "103") (name "TIM4_CH4{slash}PD15") (class "Default")
      (node (ref "PWM_R1") (pin "12") (pinfunction "12_12") (pintype "passive"))
    )
    (net (code "104") (name "TIM5_CH1{slash}PH10") (class "Default")
      (node (ref "PWM_R1") (pin "15") (pinfunction "15_15") (pintype "passive"))
    )
    (net (code "105") (name "TIM5_CH2{slash}PH11") (class "Default")
      (node (ref "PWM_R1") (pin "18") (pinfunction "18_18") (pintype "passive"))
    )
    (net (code "106") (name "TIM5_CH3{slash}PH12") (class "Default")
      (node (ref "PWM_R1") (pin "21") (pinfunction "21_21") (pintype "passive"))
    )
    (net (code "107") (name "TIM5_CH4{slash}PI0") (class "Default")
      (node (ref "PWM_R1") (pin "24") (pinfunction "24_24") (pintype "passive"))
    )
    (net (code "108") (name "TIM8_CH1{slash}PI5") (class "Default")
      (node (ref "PWM_L1") (pin "13") (pinfunction "13_13") (pintype "passive"))
    )
    (net (code "109") (name "TIM8_CH2{slash}PI6") (class "Default")
      (node (ref "PWM_L1") (pin "16") (pinfunction "16_16") (pintype "passive"))
    )
    (net (code "110") (name "TIM8_CH3{slash}PI7") (class "Default")
      (node (ref "PWM_L1") (pin "19") (pinfunction "19_19") (pintype "passive"))
    )
    (net (code "111") (name "TIM8_CH4{slash}PI2") (class "Default")
      (node (ref "PWM_L1") (pin "22") (pinfunction "22_22") (pintype "passive"))
    )
    (net (code "112") (name "TIM12_CH1{slash}PH6") (class "Default")
      (node (ref "R12") (pin "1") (pinfunction "1_1") (pintype "passive"))
    )
    (net (code "113") (name "TIM12_CH2{slash}PH9") (class "Default")
      (node (ref "U3") (pin "4") (pinfunction "B_4") (pintype "passive"))
    )
    (net (code "114") (name "UART4_RX{slash}PA1") (class "Default")
      (node (ref "Q3") (pin "3") (pinfunction "C_3") (pintype "passive"))
      (node (ref "R10") (pin "1") (pinfunction "1_1") (pintype "passive"))
    )
    (net (code "115") (name "UART7_RX{slash}PE7") (class "Default")
      (node (ref "USART3") (pin "2") (pinfunction "2_2") (pintype "passive"))
    )
    (net (code "116") (name "UART7_TX{slash}PE8") (class "Default")
      (node (ref "USART3") (pin "1") (pinfunction "1_1") (pintype "passive"))
    )
    (net (code "117") (name "UART8_RX{slash}PE0") (class "Default")
      (node (ref "USART6") (pin "2") (pinfunction "2_2") (pintype "passive"))
    )
    (net (code "118") (name "UART8_TX{slash}PE1") (class "Default")
      (node (ref "USART6") (pin "1") (pinfunction "1_1") (pintype "passive"))
    )
    (net (code "119") (name "USART1_RX{slash}PA10") (class "Default")
      (node (ref "USART1") (pin "3") (pinfunction "3_3") (pintype "passive"))
    )
    (net (code "120") (name "USART1_TX{slash}PA9") (class "Default")
      (node (ref "USART1") (pin "4") (pinfunction "4_4") (pintype "passive"))
    )
    (net (code "121") (name "USART2_RX{slash}PD6") (class "Default")
      (node (ref "USART4") (pin "3") (pinfunction "3_3") (pintype "passive"))
    )
    (net (code "122") (name "USART2_TX{slash}PD5") (class "Default")
      (node (ref "USART4") (pin "4") (pinfunction "4_4") (pintype "passive"))
    )
    (net (code "123") (name "USART3_RX{slash}PD9") (class "Default")
      (node (ref "USART5") (pin "3") (pinfunction "3_3") (pintype "passive"))
    )
    (net (code "124") (name "USART3_TX{slash}PD8") (class "Default")
      (node (ref "USART5") (pin "4") (pinfunction "4_4") (pintype "passive"))
    )
    (net (code "125") (name "USART6_RX{slash}PC7") (class "Default")
      (node (ref "USART2") (pin "2") (pinfunction "2_2") (pintype "passive"))
    )
    (net (code "126") (name "USART6_TX{slash}PC6") (class "Default")
      (node (ref "USART2") (pin "1") (pinfunction "1_1") (pintype "passive"))
    )
    (net (code "127") (name "USB_FS_DM{slash}PA11") (class "Default")
      (node (ref "R8") (pin "1") (pinfunction "1_1") (pintype "passive"))
    )
    (net (code "128") (name "USB_FS_DP{slash}PA12") (class "Default")
      (node (ref "R9") (pin "1") (pinfunction "1_1") (pintype "passive"))
    )
    (net (code "129") (name "VCC3V3") (class "Default")
      (node (ref "C2") (pin "2") (pinfunction "2_2") (pintype "passive"))
      (node (ref "R10") (pin "2") (pinfunction "2_2") (pintype "passive"))
      (node (ref "R16") (pin "1") (pinfunction "1_1") (pintype "passive"))
      (node (ref "R17") (pin "1") (pinfunction "1_1") (pintype "passive"))
      (node (ref "R18") (pin "1") (pinfunction "1_1") (pintype "passive"))
      (node (ref "R19") (pin "1") (pinfunction "1_1") (pintype "passive"))
      (node (ref "R2") (pin "1") (pinfunction "1_1") (pintype "passive"))
      (node (ref "R20") (pin "1") (pinfunction "1_1") (pintype "passive"))
      (node (ref "R21") (pin "1") (pinfunction "1_1") (pintype "passive"))
      (node (ref "R22") (pin "1") (pinfunction "1_1") (pintype "passive"))
      (node (ref "R23") (pin "1") (pinfunction "1_1") (pintype "passive"))
      (node (ref "R24") (pin "1") (pinfunction "1_1") (pintype "passive"))
      (node (ref "R25") (pin "1") (pinfunction "1_1") (pintype "passive"))
      (node (ref "R3") (pin "1") (pinfunction "1_1") (pintype "passive"))
      (node (ref "R4") (pin "1") (pinfunction "1_1") (pintype "passive"))
      (node (ref "R5") (pin "1") (pinfunction "1_1") (pintype "passive"))
      (node (ref "R6") (pin "1") (pinfunction "1_1") (pintype "passive"))
      (node (ref "RST1") (pin "1") (pinfunction "1_1") (pintype "passive"))
      (node (ref "TF_Card1") (pin "4") (pinfunction "VDD_4") (pintype "passive"))
      (node (ref "U1") (pin "6") (pinfunction "VCCB_6") (pintype "passive"))
      (node (ref "U2") (pin "6") (pinfunction "VCCB_6") (pintype "passive"))
      (node (ref "U3") (pin "6") (pinfunction "VCCB_6") (pintype "passive"))
      (node (ref "U4") (pin "6") (pinfunction "VCCB_6") (pintype "passive"))
      (node (ref "U5") (pin "6") (pinfunction "VCCB_6") (pintype "passive"))
    )
    (net (code "130") (name "VCC3V3_OLED") (class "Default")
      (node (ref "OLED1") (pin "1") (pinfunction "1_1") (pintype "passive"))
    )
    (net (code "131") (name "VCC5V") (class "Default")
      (node (ref "DBUS1") (pin "2") (pinfunction "2_2") (pintype "passive"))
      (node (ref "U3") (pin "1") (pinfunction "VCCA_1") (pintype "passive"))
    )
    (net (code "132") (name "VCC5V1A") (class "Default")
      (node (ref "C1") (pin "2") (pinfunction "2_2") (pintype "passive"))
      (node (ref "C3") (pin "2") (pinfunction "2_2") (pintype "passive"))
      (node (ref "C4") (pin "1") (pinfunction "1_1") (pintype "passive"))
      (node (ref "CAN2") (pin "4") (pinfunction "4_4") (pintype "passive"))
      (node (ref "CAN8") (pin "4") (pinfunction "4_4") (pintype "passive"))
      (node (ref "D1") (pin "2") (pinfunction "K_2") (pintype "passive"))
      (node (ref "IC1") (pin "3") (pinfunction "VDD_3") (pintype "passive"))
      (node (ref "IC_C1") (pin "2") (pinfunction "2_2") (pintype "passive"))
      (node (ref "IIC1") (pin "1") (pinfunction "1_1") (pintype "passive"))
      (node (ref "IIC2") (pin "4") (pinfunction "4_4") (pintype "passive"))
      (node (ref "IIC3") (pin "4") (pinfunction "4_4") (pintype "passive"))
      (node (ref "J1") (pin "3") (pinfunction "VCC_3") (pintype "passive"))
      (node (ref "J2") (pin "3") (pinfunction "VCC_3") (pintype "passive"))
      (node (ref "JP9") (pin "1") (pinfunction "1_1") (pintype "passive"))
      (node (ref "LASER1") (pin "1") (pinfunction "1_1") (pintype "passive"))
      (node (ref "LS1") (pin "1") (pinfunction "1_1") (pintype "passive"))
      (node (ref "SPI1") (pin "2") (pinfunction "2_2") (pintype "passive"))
      (node (ref "SPI2") (pin "5") (pinfunction "5_5") (pintype "passive"))
      (node (ref "SPI3") (pin "2") (pinfunction "2_2") (pintype "passive"))
      (node (ref "SPI4") (pin "2") (pinfunction "2_2") (pintype "passive"))
      (node (ref "U1") (pin "1") (pinfunction "VCCA_1") (pintype "passive"))
      (node (ref "U2") (pin "1") (pinfunction "VCCA_1") (pintype "passive"))
      (node (ref "U4") (pin "1") (pinfunction "VCCA_1") (pintype "passive"))
      (node (ref "U5") (pin "1") (pinfunction "VCCA_1") (pintype "passive"))
      (node (ref "USART1") (pin "1") (pinfunction "1_1") (pintype "passive"))
      (node (ref "USART2") (pin "4") (pinfunction "4_4") (pintype "passive"))
      (node (ref "USART3") (pin "4") (pinfunction "4_4") (pintype "passive"))
      (node (ref "USART4") (pin "1") (pinfunction "1_1") (pintype "passive"))
      (node (ref "USART5") (pin "1") (pinfunction "1_1") (pintype "passive"))
      (node (ref "USART6") (pin "4") (pinfunction "4_4") (pintype "passive"))
      (node (ref "USB1") (pin "A4") (pinfunction "VBUS_A4") (pintype "passive"))
      (node (ref "USB1") (pin "A9") (pinfunction "VBUS_A9") (pintype "passive"))
      (node (ref "USB1") (pin "B4") (pinfunction "VBUS_B4") (pintype "passive"))
      (node (ref "USB1") (pin "B9") (pinfunction "VBUS_B9") (pintype "passive"))
    )
    (net (code "133") (name "VCC5V4A") (class "Default")
      (node (ref "JP1") (pin "1") (pinfunction "1_1") (pintype "passive"))
      (node (ref "JP2") (pin "2") (pinfunction "2_2") (pintype "passive"))
      (node (ref "JP3") (pin "2") (pinfunction "2_2") (pintype "passive"))
      (node (ref "JP4") (pin "2") (pinfunction "2_2") (pintype "passive"))
      (node (ref "JP5") (pin "2") (pinfunction "2_2") (pintype "passive"))
      (node (ref "JP6") (pin "2") (pinfunction "2_2") (pintype "passive"))
      (node (ref "JP7") (pin "2") (pinfunction "2_2") (pintype "passive"))
      (node (ref "JP8") (pin "2") (pinfunction "2_2") (pintype "passive"))
      (node (ref "PWM_L1") (pin "11") (pinfunction "11_11") (pintype "passive"))
      (node (ref "PWM_L1") (pin "14") (pinfunction "14_14") (pintype "passive"))
      (node (ref "PWM_L1") (pin "17") (pinfunction "17_17") (pintype "passive"))
      (node (ref "PWM_L1") (pin "2") (pinfunction "2_2") (pintype "passive"))
      (node (ref "PWM_L1") (pin "20") (pinfunction "20_20") (pintype "passive"))
      (node (ref "PWM_L1") (pin "23") (pinfunction "23_23") (pintype "passive"))
      (node (ref "PWM_L1") (pin "5") (pinfunction "5_5") (pintype "passive"))
      (node (ref "PWM_L1") (pin "8") (pinfunction "8_8") (pintype "passive"))
      (node (ref "PWM_R1") (pin "11") (pinfunction "11_11") (pintype "passive"))
      (node (ref "PWM_R1") (pin "14") (pinfunction "14_14") (pintype "passive"))
      (node (ref "PWM_R1") (pin "17") (pinfunction "17_17") (pintype "passive"))
      (node (ref "PWM_R1") (pin "2") (pinfunction "2_2") (pintype "passive"))
      (node (ref "PWM_R1") (pin "20") (pinfunction "20_20") (pintype "passive"))
      (node (ref "PWM_R1") (pin "23") (pinfunction "23_23") (pintype "passive"))
      (node (ref "PWM_R1") (pin "5") (pinfunction "5_5") (pintype "passive"))
      (node (ref "PWM_R1") (pin "8") (pinfunction "8_8") (pintype "passive"))
    )
    (net (code "134") (name "WKUP{slash}PA0") (class "Default")
      (node (ref "RST1") (pin "2") (pinfunction "2_2") (pintype "passive"))
    )
    (net (code "135") (name "unconnected-(IC1-DOUT-Pad4)") (class "Default")
      (node (ref "IC1") (pin "4") (pinfunction "DOUT_4") (pintype "passive+no_connect"))
    )
    (net (code "136") (name "unconnected-(J1-Vref-Pad5)") (class "Default")
      (node (ref "J1") (pin "5") (pinfunction "Vref_5") (pintype "passive+no_connect"))
    )
    (net (code "137") (name "unconnected-(J2-Vref-Pad5)") (class "Default")
      (node (ref "J2") (pin "5") (pinfunction "Vref_5") (pintype "passive+no_connect"))
    )
    (net (code "138") (name "unconnected-(LS1-Pad3)") (class "Default")
      (node (ref "LS1") (pin "3") (pinfunction "3_3") (pintype "passive+no_connect"))
    )
    (net (code "139") (name "unconnected-(TF_Card1-K-Pad9)") (class "Default")
      (node (ref "TF_Card1") (pin "9") (pinfunction "K_9") (pintype "passive+no_connect"))
    )
    (net (code "140") (name "unconnected-(USB1-CC1-PadA5)") (class "Default")
      (node (ref "USB1") (pin "A5") (pinfunction "CC1_A5") (pintype "passive"))
    )
    (net (code "141") (name "unconnected-(USB1-CC2-PadB5)") (class "Default")
      (node (ref "USB1") (pin "B5") (pinfunction "CC2_B5") (pintype "passive"))
    )
    (net (code "142") (name "unconnected-(USB1-RX1+-PadB11)") (class "Default")
      (node (ref "USB1") (pin "B11") (pinfunction "RX1+_B11") (pintype "passive"))
    )
    (net (code "143") (name "unconnected-(USB1-RX1--PadB10)") (class "Default")
      (node (ref "USB1") (pin "B10") (pinfunction "RX1-_B10") (pintype "passive"))
    )
    (net (code "144") (name "unconnected-(USB1-RX2+-PadA11)") (class "Default")
      (node (ref "USB1") (pin "A11") (pinfunction "RX2+_A11") (pintype "passive"))
    )
    (net (code "145") (name "unconnected-(USB1-RX2--PadA10)") (class "Default")
      (node (ref "USB1") (pin "A10") (pinfunction "RX2-_A10") (pintype "passive"))
    )
    (net (code "146") (name "unconnected-(USB1-SBU1-PadA8)") (class "Default")
      (node (ref "USB1") (pin "A8") (pinfunction "SBU1_A8") (pintype "passive"))
    )
    (net (code "147") (name "unconnected-(USB1-SBU2-PadB8)") (class "Default")
      (node (ref "USB1") (pin "B8") (pinfunction "SBU2_B8") (pintype "passive"))
    )
    (net (code "148") (name "unconnected-(USB1-SH1-Pad1)") (class "Default")
      (node (ref "USB1") (pin "1") (pinfunction "SH1_1") (pintype "passive"))
    )
    (net (code "149") (name "unconnected-(USB1-SH2-Pad2)") (class "Default")
      (node (ref "USB1") (pin "2") (pinfunction "SH2_2") (pintype "passive"))
    )
    (net (code "150") (name "unconnected-(USB1-SH3-Pad3)") (class "Default")
      (node (ref "USB1") (pin "3") (pinfunction "SH3_3") (pintype "passive"))
    )
    (net (code "151") (name "unconnected-(USB1-SH4-Pad4)") (class "Default")
      (node (ref "USB1") (pin "4") (pinfunction "SH4_4") (pintype "passive"))
    )
    (net (code "152") (name "unconnected-(USB1-TX1+-PadA2)") (class "Default")
      (node (ref "USB1") (pin "A2") (pinfunction "TX1+_A2") (pintype "passive"))
    )
    (net (code "153") (name "unconnected-(USB1-TX1--PadA3)") (class "Default")
      (node (ref "USB1") (pin "A3") (pinfunction "TX1-_A3") (pintype "passive"))
    )
    (net (code "154") (name "unconnected-(USB1-TX2+-PadB2)") (class "Default")
      (node (ref "USB1") (pin "B2") (pinfunction "TX2+_B2") (pintype "passive"))
    )
    (net (code "155") (name "unconnected-(USB1-TX2--PadB3)") (class "Default")
      (node (ref "USB1") (pin "B3") (pinfunction "TX2-_B3") (pintype "passive"))
    )
  )
)
